# S7CAS-PLEIADES-CARTE-MERE_P20_PLL.net
KiCad netlist of a schematic drawn in Altium Designer
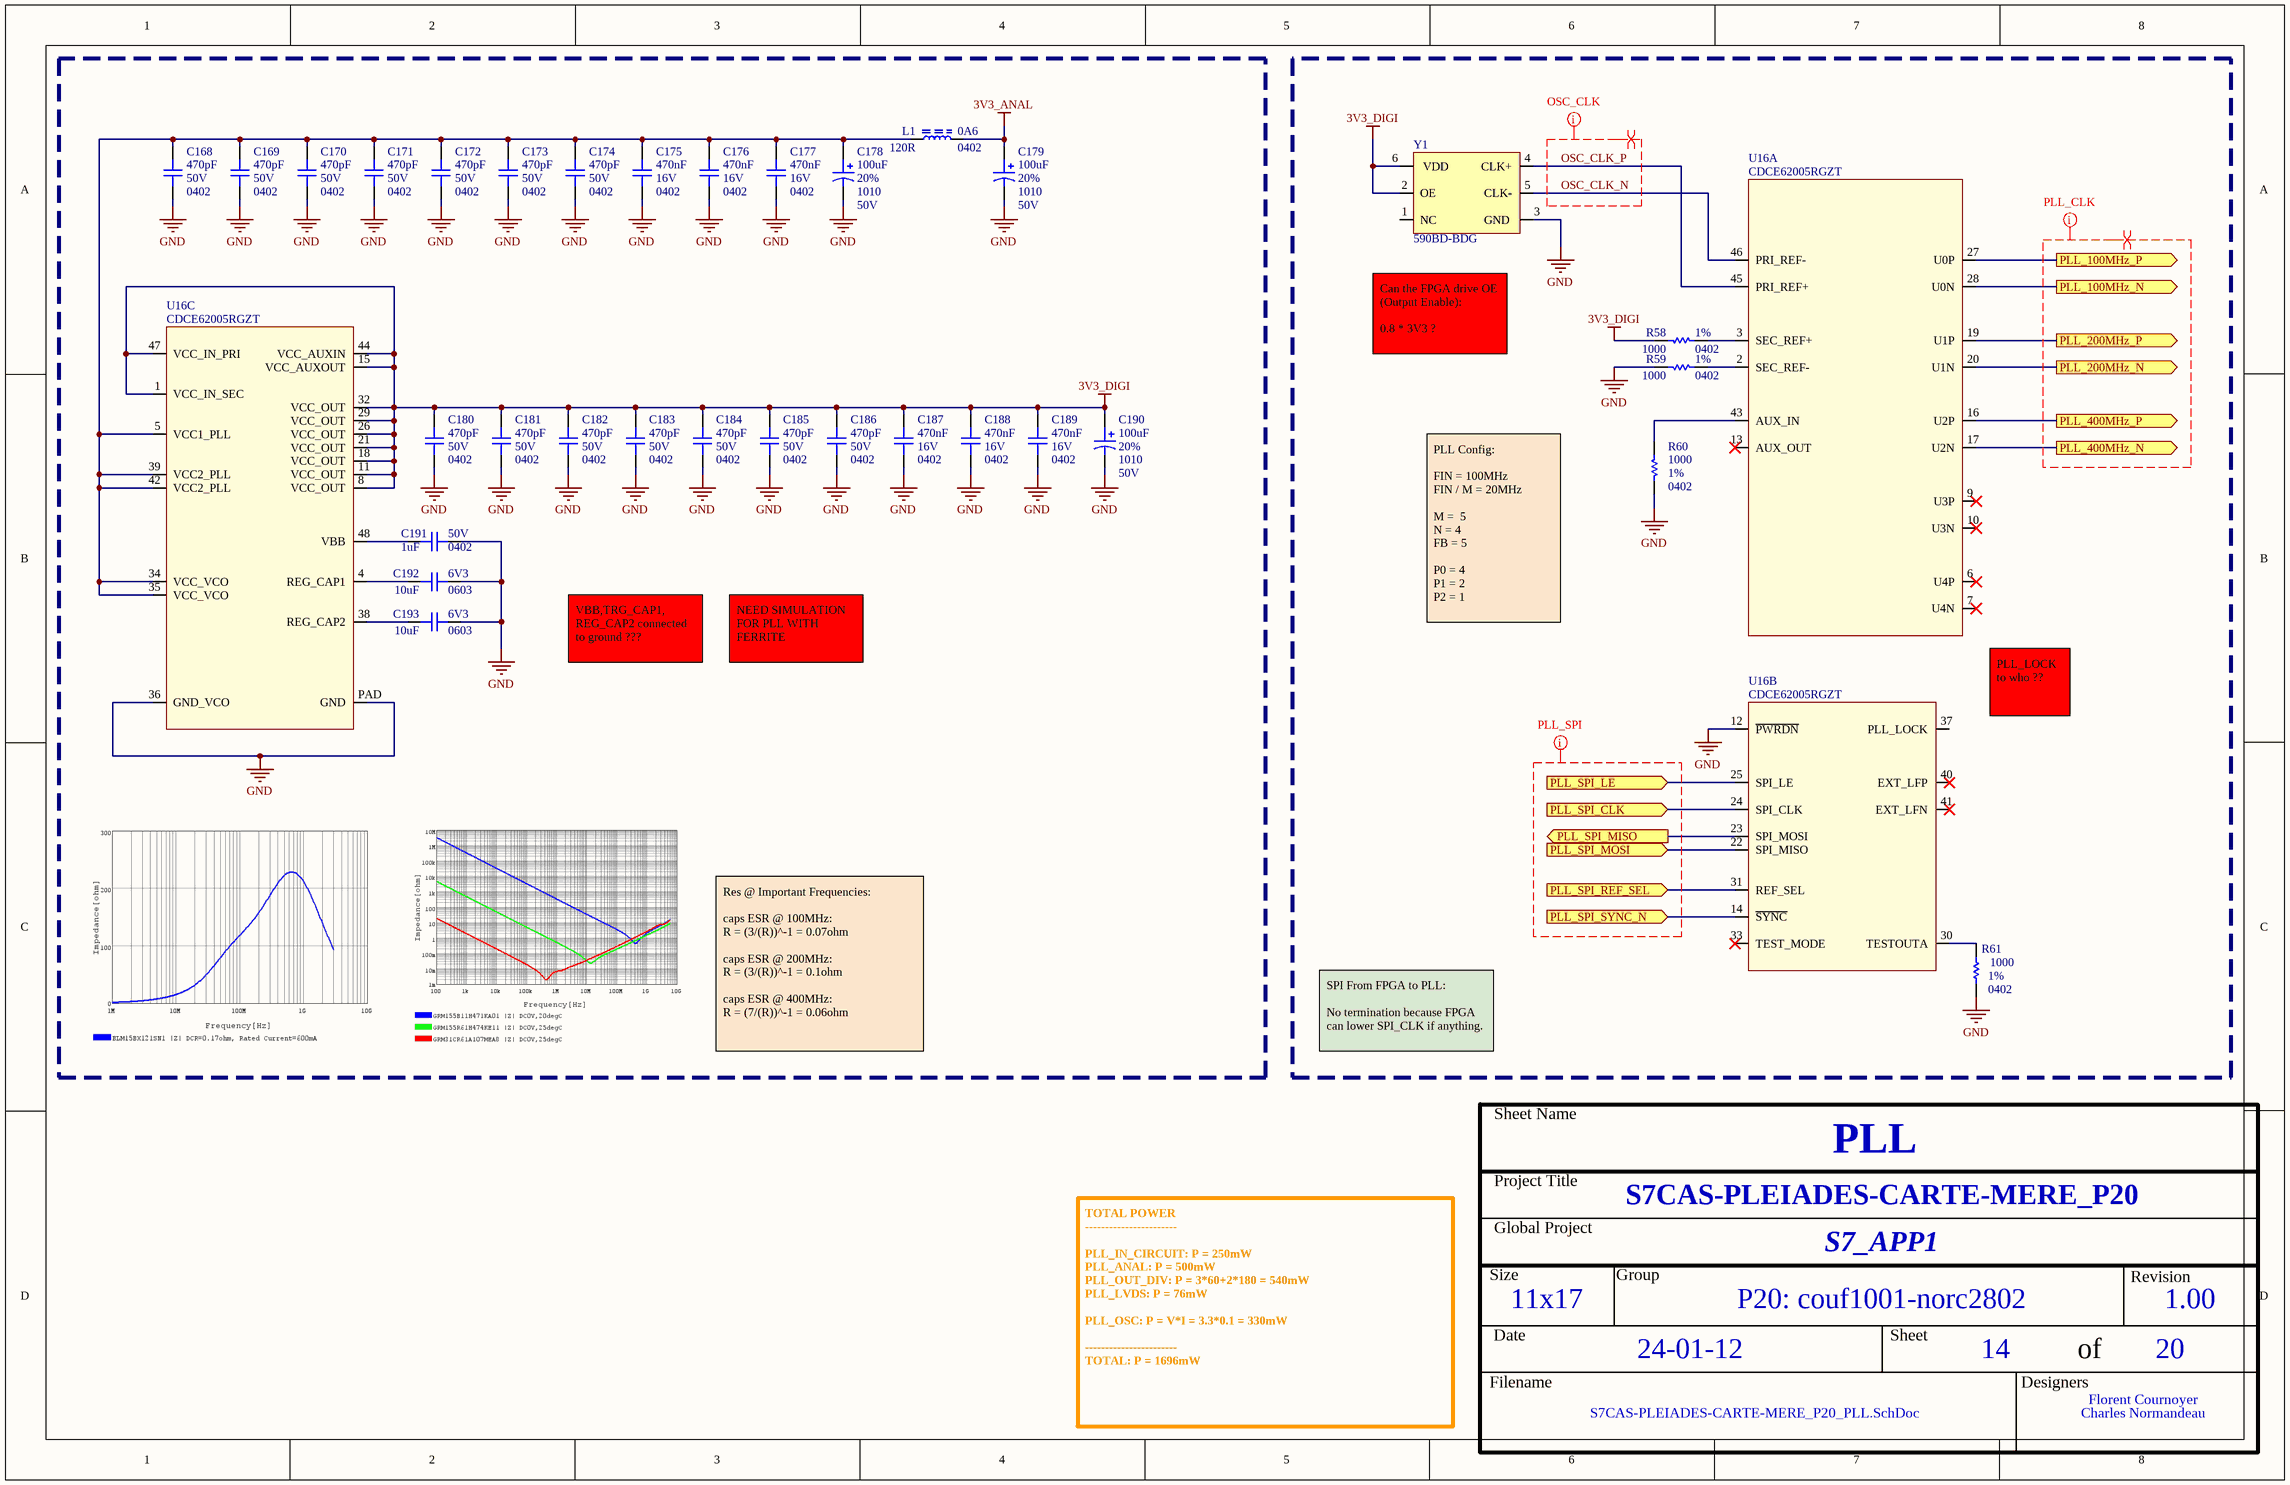
[diagram p0: S7CAS-PLEIADES-CARTE-MERE_P20_PLL.SchDoc]

(export (version "E")
  (design (tool "Eeschema 10.0.6"))
  (components
    (comp (ref "C168")
      (value "470pF")
      (footprint "CAP_0402")
      (description "CAP - 0402")
      (fields
        (field (name "MFG PART NUMBER") "GRM155B11H471KA01")
        (field (name "VOLTAGE") "50V")
        (field (name "PACKAGE") "0402")
        (field (name "CREATEDBY") "Jonathan Bouchard")
      )
      (libsource (lib "S7CAS_LIB2023") (part "CAP - 0402"))
    )
    (comp (ref "C169")
      (value "470pF")
      (footprint "CAP_0402")
      (description "CAP - 0402")
      (fields
        (field (name "MFG PART NUMBER") "GRM155B11H471KA01")
        (field (name "VOLTAGE") "50V")
        (field (name "PACKAGE") "0402")
        (field (name "CREATEDBY") "Jonathan Bouchard")
      )
      (libsource (lib "S7CAS_LIB2023") (part "CAP - 0402"))
    )
    (comp (ref "C170")
      (value "470pF")
      (footprint "CAP_0402")
      (description "CAP - 0402")
      (fields
        (field (name "MFG PART NUMBER") "GRM155B11H471KA01")
        (field (name "VOLTAGE") "50V")
        (field (name "PACKAGE") "0402")
        (field (name "CREATEDBY") "Jonathan Bouchard")
      )
      (libsource (lib "S7CAS_LIB2023") (part "CAP - 0402"))
    )
    (comp (ref "C171")
      (value "470pF")
      (footprint "CAP_0402")
      (description "CAP - 0402")
      (fields
        (field (name "MFG PART NUMBER") "GRM155B11H471KA01")
        (field (name "VOLTAGE") "50V")
        (field (name "PACKAGE") "0402")
        (field (name "CREATEDBY") "Jonathan Bouchard")
      )
      (libsource (lib "S7CAS_LIB2023") (part "CAP - 0402"))
    )
    (comp (ref "C172")
      (value "470pF")
      (footprint "CAP_0402")
      (description "CAP - 0402")
      (fields
        (field (name "MFG PART NUMBER") "GRM155B11H471KA01")
        (field (name "VOLTAGE") "50V")
        (field (name "PACKAGE") "0402")
        (field (name "CREATEDBY") "Jonathan Bouchard")
      )
      (libsource (lib "S7CAS_LIB2023") (part "CAP - 0402"))
    )
    (comp (ref "C173")
      (value "470pF")
      (footprint "CAP_0402")
      (description "CAP - 0402")
      (fields
        (field (name "MFG PART NUMBER") "GRM155B11H471KA01")
        (field (name "VOLTAGE") "50V")
        (field (name "PACKAGE") "0402")
        (field (name "CREATEDBY") "Jonathan Bouchard")
      )
      (libsource (lib "S7CAS_LIB2023") (part "CAP - 0402"))
    )
    (comp (ref "C174")
      (value "470pF")
      (footprint "CAP_0402")
      (description "CAP - 0402")
      (fields
        (field (name "MFG PART NUMBER") "GRM155B11H471KA01")
        (field (name "VOLTAGE") "50V")
        (field (name "PACKAGE") "0402")
        (field (name "CREATEDBY") "Jonathan Bouchard")
      )
      (libsource (lib "S7CAS_LIB2023") (part "CAP - 0402"))
    )
    (comp (ref "C175")
      (value "470nF")
      (footprint "CAP_0402")
      (description "CAP - 0402")
      (fields
        (field (name "MFG PART NUMBER") "GXT155R61C474KE01")
        (field (name "VOLTAGE") "16V")
        (field (name "PACKAGE") "0402")
        (field (name "CREATEDBY") "Jonathan Bouchard")
      )
      (libsource (lib "S7CAS_LIB2023") (part "CAP - 0402"))
    )
    (comp (ref "C176")
      (value "470nF")
      (footprint "CAP_0402")
      (description "CAP - 0402")
      (fields
        (field (name "MFG PART NUMBER") "GXT155R61C474KE01")
        (field (name "VOLTAGE") "16V")
        (field (name "PACKAGE") "0402")
        (field (name "CREATEDBY") "Jonathan Bouchard")
      )
      (libsource (lib "S7CAS_LIB2023") (part "CAP - 0402"))
    )
    (comp (ref "C177")
      (value "470nF")
      (footprint "CAP_0402")
      (description "CAP - 0402")
      (fields
        (field (name "MFG PART NUMBER") "GXT155R61C474KE01")
        (field (name "VOLTAGE") "16V")
        (field (name "PACKAGE") "0402")
        (field (name "CREATEDBY") "Jonathan Bouchard")
      )
      (libsource (lib "S7CAS_LIB2023") (part "CAP - 0402"))
    )
    (comp (ref "C178")
      (value "100uF")
      (footprint "CAP_ALU_1010_vishay")
      (description "CAP - ALU 100uF 20% 50V - 1010")
      (fields
        (field (name "MFG") "Vishay Dale")
        (field (name "MFG PART NUMBER") "MAL215099101E3")
        (field (name "VOLTAGE") "50V")
        (field (name "PACKAGE") "1010")
        (field (name "PRECISION") "20%")
        (field (name "CREATEDBY") "Jonathan Bouchard")
      )
      (libsource (lib "S7CAS_LIB2023") (part "CAP_ALU_MAL215099101E3"))
    )
    (comp (ref "C179")
      (value "100uF")
      (footprint "CAP_ALU_1010_vishay")
      (description "CAP - ALU 100uF 20% 50V - 1010")
      (fields
        (field (name "MFG") "Vishay Dale")
        (field (name "MFG PART NUMBER") "MAL215099101E3")
        (field (name "VOLTAGE") "50V")
        (field (name "PACKAGE") "1010")
        (field (name "PRECISION") "20%")
        (field (name "CREATEDBY") "Jonathan Bouchard")
      )
      (libsource (lib "S7CAS_LIB2023") (part "CAP_ALU_MAL215099101E3"))
    )
    (comp (ref "C180")
      (value "470pF")
      (footprint "CAP_0402")
      (description "CAP - 0402")
      (fields
        (field (name "MFG PART NUMBER") "GRM155B11H471KA01")
        (field (name "VOLTAGE") "50V")
        (field (name "PACKAGE") "0402")
        (field (name "CREATEDBY") "Jonathan Bouchard")
      )
      (libsource (lib "S7CAS_LIB2023") (part "CAP - 0402"))
    )
    (comp (ref "C181")
      (value "470pF")
      (footprint "CAP_0402")
      (description "CAP - 0402")
      (fields
        (field (name "MFG PART NUMBER") "GRM155B11H471KA01")
        (field (name "VOLTAGE") "50V")
        (field (name "PACKAGE") "0402")
        (field (name "CREATEDBY") "Jonathan Bouchard")
      )
      (libsource (lib "S7CAS_LIB2023") (part "CAP - 0402"))
    )
    (comp (ref "C182")
      (value "470pF")
      (footprint "CAP_0402")
      (description "CAP - 0402")
      (fields
        (field (name "MFG PART NUMBER") "GRM155B11H471KA01")
        (field (name "VOLTAGE") "50V")
        (field (name "PACKAGE") "0402")
        (field (name "CREATEDBY") "Jonathan Bouchard")
      )
      (libsource (lib "S7CAS_LIB2023") (part "CAP - 0402"))
    )
    (comp (ref "C183")
      (value "470pF")
      (footprint "CAP_0402")
      (description "CAP - 0402")
      (fields
        (field (name "MFG PART NUMBER") "GRM155B11H471KA01")
        (field (name "VOLTAGE") "50V")
        (field (name "PACKAGE") "0402")
        (field (name "CREATEDBY") "Jonathan Bouchard")
      )
      (libsource (lib "S7CAS_LIB2023") (part "CAP - 0402"))
    )
    (comp (ref "C184")
      (value "470pF")
      (footprint "CAP_0402")
      (description "CAP - 0402")
      (fields
        (field (name "MFG PART NUMBER") "GRM155B11H471KA01")
        (field (name "VOLTAGE") "50V")
        (field (name "PACKAGE") "0402")
        (field (name "CREATEDBY") "Jonathan Bouchard")
      )
      (libsource (lib "S7CAS_LIB2023") (part "CAP - 0402"))
    )
    (comp (ref "C185")
      (value "470pF")
      (footprint "CAP_0402")
      (description "CAP - 0402")
      (fields
        (field (name "MFG PART NUMBER") "GRM155B11H471KA01")
        (field (name "VOLTAGE") "50V")
        (field (name "PACKAGE") "0402")
        (field (name "CREATEDBY") "Jonathan Bouchard")
      )
      (libsource (lib "S7CAS_LIB2023") (part "CAP - 0402"))
    )
    (comp (ref "C186")
      (value "470pF")
      (footprint "CAP_0402")
      (description "CAP - 0402")
      (fields
        (field (name "MFG PART NUMBER") "GRM155B11H471KA01")
        (field (name "VOLTAGE") "50V")
        (field (name "PACKAGE") "0402")
        (field (name "CREATEDBY") "Jonathan Bouchard")
      )
      (libsource (lib "S7CAS_LIB2023") (part "CAP - 0402"))
    )
    (comp (ref "C187")
      (value "470nF")
      (footprint "CAP_0402")
      (description "CAP - 0402")
      (fields
        (field (name "MFG PART NUMBER") "GXT155R61C474KE01")
        (field (name "VOLTAGE") "16V")
        (field (name "PACKAGE") "0402")
        (field (name "CREATEDBY") "Jonathan Bouchard")
      )
      (libsource (lib "S7CAS_LIB2023") (part "CAP - 0402"))
    )
    (comp (ref "C188")
      (value "470nF")
      (footprint "CAP_0402")
      (description "CAP - 0402")
      (fields
        (field (name "MFG PART NUMBER") "GXT155R61C474KE01")
        (field (name "VOLTAGE") "16V")
        (field (name "PACKAGE") "0402")
        (field (name "CREATEDBY") "Jonathan Bouchard")
      )
      (libsource (lib "S7CAS_LIB2023") (part "CAP - 0402"))
    )
    (comp (ref "C189")
      (value "470nF")
      (footprint "CAP_0402")
      (description "CAP - 0402")
      (fields
        (field (name "MFG PART NUMBER") "GXT155R61C474KE01")
        (field (name "VOLTAGE") "16V")
        (field (name "PACKAGE") "0402")
        (field (name "CREATEDBY") "Jonathan Bouchard")
      )
      (libsource (lib "S7CAS_LIB2023") (part "CAP - 0402"))
    )
    (comp (ref "C190")
      (value "100uF")
      (footprint "CAP_ALU_1010_vishay")
      (description "CAP - ALU 100uF 20% 50V - 1010")
      (fields
        (field (name "MFG") "Vishay Dale")
        (field (name "MFG PART NUMBER") "MAL215099101E3")
        (field (name "VOLTAGE") "50V")
        (field (name "PACKAGE") "1010")
        (field (name "PRECISION") "20%")
        (field (name "CREATEDBY") "Jonathan Bouchard")
      )
      (libsource (lib "S7CAS_LIB2023") (part "CAP_ALU_MAL215099101E3"))
    )
    (comp (ref "C191")
      (value "1uF")
      (footprint "CAP_0402")
      (description "CAP - 0402")
      (fields
        (field (name "MFG PART NUMBER") "GXT155R61E105KE01")
        (field (name "VOLTAGE") "50V")
        (field (name "PACKAGE") "0402")
        (field (name "CREATEDBY") "Jonathan Bouchard")
      )
      (libsource (lib "S7CAS_LIB2023") (part "CAP - 0402"))
    )
    (comp (ref "C192")
      (value "10uF")
      (footprint "CAP_0603")
      (description "CAP - 0603")
      (fields
        (field (name "MFG PART NUMBER") "GRM185R60J106ME15")
        (field (name "VOLTAGE") "6V3")
        (field (name "PACKAGE") "0603")
        (field (name "CREATEDBY") "Jonathan Bouchard")
      )
      (libsource (lib "S7CAS_LIB2023") (part "CAP - 0603"))
    )
    (comp (ref "C193")
      (value "10uF")
      (footprint "CAP_0603")
      (description "CAP - 0603")
      (fields
        (field (name "MFG PART NUMBER") "GRM185R60J106ME15")
        (field (name "VOLTAGE") "6V3")
        (field (name "PACKAGE") "0603")
        (field (name "CREATEDBY") "Jonathan Bouchard")
      )
      (libsource (lib "S7CAS_LIB2023") (part "CAP - 0603"))
    )
    (comp (ref "L1")
      (value "120R")
      (footprint "FER_0402")
      (description "FER - 0402")
      (fields
        (field (name "MFG PART NUMBER") "BLM15BX121SN1")
        (field (name "CURRENT") "0A6")
        (field (name "PACKAGE") "0402")
        (field (name "CREATEDBY") "Jonathan Bouchard")
      )
      (libsource (lib "S7CAS_LIB2023") (part "FER - 0402"))
    )
    (comp (ref "R58")
      (value "1000")
      (footprint "RES_0402")
      (description "RES - 0402")
      (fields
        (field (name "VOLTAGE") "50V")
        (field (name "MFG PART NUMBER") "MCS04020C1001FE000")
        (field (name "PACKAGE") "0402")
        (field (name "PRECISION") "1%")
        (field (name "CREATEDBY") "Jonathan Bouchard")
      )
      (libsource (lib "S7CAS_LIB2023") (part "RES - 0402"))
    )
    (comp (ref "R59")
      (value "1000")
      (footprint "RES_0402")
      (description "RES - 0402")
      (fields
        (field (name "VOLTAGE") "50V")
        (field (name "MFG PART NUMBER") "MCS04020C1001FE000")
        (field (name "PACKAGE") "0402")
        (field (name "PRECISION") "1%")
        (field (name "CREATEDBY") "Jonathan Bouchard")
      )
      (libsource (lib "S7CAS_LIB2023") (part "RES - 0402"))
    )
    (comp (ref "R60")
      (value "1000")
      (footprint "RES_0402")
      (description "RES - 0402")
      (fields
        (field (name "VOLTAGE") "50V")
        (field (name "MFG PART NUMBER") "MCS04020C1001FE000")
        (field (name "PACKAGE") "0402")
        (field (name "PRECISION") "1%")
        (field (name "CREATEDBY") "Jonathan Bouchard")
      )
      (libsource (lib "S7CAS_LIB2023") (part "RES - 0402"))
    )
    (comp (ref "R61")
      (value "1000")
      (footprint "RES_0402")
      (description "RES - 0402")
      (fields
        (field (name "VOLTAGE") "50V")
        (field (name "MFG PART NUMBER") "MCS04020C1001FE000")
        (field (name "PACKAGE") "0402")
        (field (name "PRECISION") "1%")
        (field (name "CREATEDBY") "Jonathan Bouchard")
      )
      (libsource (lib "S7CAS_LIB2023") (part "RES - 0402"))
    )
    (comp (ref "U16")
      (value "CDCE62005RGZT")
      (footprint "TIM_CDCE62005RGZT")
      (description "TIM - CLK SYNTH JITTER CLEANER 3:5 - QFN-48")
      (fields
        (field (name "VOLTAGE") "3 V ~ 3.6 V")
        (field (name "MFG") "Texas Instruments")
        (field (name "CREATEDBY") "Jonathan Bouchard")
      )
      (libsource (lib "S7CAS_LIB2023") (part "TIM_CDCE62005RGZT"))
    )
    (comp (ref "Y1")
      (value "590BD-BDG")
      (footprint "OSC_590BD-BDG")
      (description "TIM - OSC PROG 125MHz ~ 214.999MHz LVDS 3.3V 7PPM EN/DS - 6-SMD")
      (fields
        (field (name "CREATEDBY/DATE") "from 590BD-CDG")
        (field (name "VERIFIEDBY") "Caroline Paulin / 3/10/2019")
      )
      (libsource (lib "S7CAS_LIB2023") (part "OSC_590BD-BDG"))
    )
  )
  (nets
    (net (code "1") (name "/OSC_CLK_N") (class "Default")
      (node (ref "U16") (pin "46") (pinfunction "PRI_REF-_46") (pintype "passive"))
      (node (ref "Y1") (pin "5") (pinfunction "CLK-_5") (pintype "passive"))
    )
    (net (code "2") (name "/OSC_CLK_P") (class "Default")
      (node (ref "U16") (pin "45") (pinfunction "PRI_REF+_45") (pintype "passive"))
      (node (ref "Y1") (pin "4") (pinfunction "CLK+_4") (pintype "passive"))
    )
    (net (code "3") (name "/PLL_100MHz_N") (class "Default")
      (node (ref "U16") (pin "28") (pinfunction "U0N_28") (pintype "passive"))
    )
    (net (code "4") (name "/PLL_100MHz_P") (class "Default")
      (node (ref "U16") (pin "27") (pinfunction "U0P_27") (pintype "passive"))
    )
    (net (code "5") (name "/PLL_200MHz_N") (class "Default")
      (node (ref "U16") (pin "20") (pinfunction "U1N_20") (pintype "passive"))
    )
    (net (code "6") (name "/PLL_200MHz_P") (class "Default")
      (node (ref "U16") (pin "19") (pinfunction "U1P_19") (pintype "passive"))
    )
    (net (code "7") (name "/PLL_400MHz_N") (class "Default")
      (node (ref "U16") (pin "17") (pinfunction "U2N_17") (pintype "passive"))
    )
    (net (code "8") (name "/PLL_400MHz_P") (class "Default")
      (node (ref "U16") (pin "16") (pinfunction "U2P_16") (pintype "passive"))
    )
    (net (code "9") (name "/PLL_SPI_CLK") (class "Default")
      (node (ref "U16") (pin "24") (pinfunction "SPI_CLK_24") (pintype "passive"))
    )
    (net (code "10") (name "/PLL_SPI_LE") (class "Default")
      (node (ref "U16") (pin "25") (pinfunction "SPI_LE_25") (pintype "passive"))
    )
    (net (code "11") (name "/PLL_SPI_MISO") (class "Default")
      (node (ref "U16") (pin "23") (pinfunction "SPI_MOSI_23") (pintype "passive"))
    )
    (net (code "12") (name "/PLL_SPI_MOSI") (class "Default")
      (node (ref "U16") (pin "22") (pinfunction "SPI_MISO_22") (pintype "passive"))
    )
    (net (code "13") (name "/PLL_SPI_REF_SEL") (class "Default")
      (node (ref "U16") (pin "31") (pinfunction "REF_SEL_31") (pintype "passive"))
    )
    (net (code "14") (name "/PLL_SPI_SYNC_N") (class "Default")
      (node (ref "U16") (pin "14") (pinfunction "~{SYNC}_14") (pintype "passive"))
    )
    (net (code "15") (name "3V3_ANAL") (class "Default")
      (node (ref "C179") (pin "1") (pinfunction "1_1") (pintype "passive"))
      (node (ref "L1") (pin "1") (pinfunction "1_1") (pintype "passive"))
    )
    (net (code "16") (name "3V3_DIGI") (class "Default")
      (node (ref "C180") (pin "2") (pinfunction "2_2") (pintype "passive"))
      (node (ref "C181") (pin "2") (pinfunction "2_2") (pintype "passive"))
      (node (ref "C182") (pin "2") (pinfunction "2_2") (pintype "passive"))
      (node (ref "C183") (pin "2") (pinfunction "2_2") (pintype "passive"))
      (node (ref "C184") (pin "2") (pinfunction "2_2") (pintype "passive"))
      (node (ref "C185") (pin "2") (pinfunction "2_2") (pintype "passive"))
      (node (ref "C186") (pin "2") (pinfunction "2_2") (pintype "passive"))
      (node (ref "C187") (pin "2") (pinfunction "2_2") (pintype "passive"))
      (node (ref "C188") (pin "2") (pinfunction "2_2") (pintype "passive"))
      (node (ref "C189") (pin "2") (pinfunction "2_2") (pintype "passive"))
      (node (ref "C190") (pin "1") (pinfunction "1_1") (pintype "passive"))
      (node (ref "R58") (pin "2") (pinfunction "2_2") (pintype "passive"))
      (node (ref "U16") (pin "1") (pinfunction "VCC_IN_SEC_1") (pintype "passive"))
      (node (ref "U16") (pin "11") (pinfunction "VCC_OUT_11") (pintype "passive"))
      (node (ref "U16") (pin "15") (pinfunction "VCC_AUXOUT_15") (pintype "passive"))
      (node (ref "U16") (pin "18") (pinfunction "VCC_OUT_18") (pintype "passive"))
      (node (ref "U16") (pin "21") (pinfunction "VCC_OUT_21") (pintype "passive"))
      (node (ref "U16") (pin "26") (pinfunction "VCC_OUT_26") (pintype "passive"))
      (node (ref "U16") (pin "29") (pinfunction "VCC_OUT_29") (pintype "passive"))
      (node (ref "U16") (pin "32") (pinfunction "VCC_OUT_32") (pintype "passive"))
      (node (ref "U16") (pin "44") (pinfunction "VCC_AUXIN_44") (pintype "passive"))
      (node (ref "U16") (pin "47") (pinfunction "VCC_IN_PRI_47") (pintype "passive"))
      (node (ref "U16") (pin "8") (pinfunction "VCC_OUT_8") (pintype "passive"))
      (node (ref "Y1") (pin "2") (pinfunction "OE_2") (pintype "passive"))
      (node (ref "Y1") (pin "6") (pinfunction "VDD_6") (pintype "passive"))
    )
    (net (code "17") (name "GND") (class "Default")
      (node (ref "C168") (pin "1") (pinfunction "1_1") (pintype "passive"))
      (node (ref "C169") (pin "1") (pinfunction "1_1") (pintype "passive"))
      (node (ref "C170") (pin "1") (pinfunction "1_1") (pintype "passive"))
      (node (ref "C171") (pin "1") (pinfunction "1_1") (pintype "passive"))
      (node (ref "C172") (pin "1") (pinfunction "1_1") (pintype "passive"))
      (node (ref "C173") (pin "1") (pinfunction "1_1") (pintype "passive"))
      (node (ref "C174") (pin "1") (pinfunction "1_1") (pintype "passive"))
      (node (ref "C175") (pin "1") (pinfunction "1_1") (pintype "passive"))
      (node (ref "C176") (pin "1") (pinfunction "1_1") (pintype "passive"))
      (node (ref "C177") (pin "1") (pinfunction "1_1") (pintype "passive"))
      (node (ref "C178") (pin "2") (pinfunction "2_2") (pintype "passive"))
      (node (ref "C179") (pin "2") (pinfunction "2_2") (pintype "passive"))
      (node (ref "C180") (pin "1") (pinfunction "1_1") (pintype "passive"))
      (node (ref "C181") (pin "1") (pinfunction "1_1") (pintype "passive"))
      (node (ref "C182") (pin "1") (pinfunction "1_1") (pintype "passive"))
      (node (ref "C183") (pin "1") (pinfunction "1_1") (pintype "passive"))
      (node (ref "C184") (pin "1") (pinfunction "1_1") (pintype "passive"))
      (node (ref "C185") (pin "1") (pinfunction "1_1") (pintype "passive"))
      (node (ref "C186") (pin "1") (pinfunction "1_1") (pintype "passive"))
      (node (ref "C187") (pin "1") (pinfunction "1_1") (pintype "passive"))
      (node (ref "C188") (pin "1") (pinfunction "1_1") (pintype "passive"))
      (node (ref "C189") (pin "1") (pinfunction "1_1") (pintype "passive"))
      (node (ref "C190") (pin "2") (pinfunction "2_2") (pintype "passive"))
      (node (ref "C191") (pin "1") (pinfunction "1_1") (pintype "passive"))
      (node (ref "C192") (pin "1") (pinfunction "1_1") (pintype "passive"))
      (node (ref "C193") (pin "1") (pinfunction "1_1") (pintype "passive"))
      (node (ref "R59") (pin "1") (pinfunction "1_1") (pintype "passive"))
      (node (ref "R60") (pin "2") (pinfunction "2_2") (pintype "passive"))
      (node (ref "R61") (pin "1") (pinfunction "1_1") (pintype "passive"))
      (node (ref "U16") (pin "12") (pinfunction "~{PWRDN}_12") (pintype "passive"))
      (node (ref "U16") (pin "36") (pinfunction "GND_VCO_36") (pintype "passive"))
      (node (ref "U16") (pin "PAD") (pinfunction "GND_PAD") (pintype "passive"))
      (node (ref "Y1") (pin "3") (pinfunction "GND_3") (pintype "passive"))
    )
    (net (code "18") (name "Net-(U16A-AUX_IN)") (class "Default")
      (node (ref "R60") (pin "1") (pinfunction "1_1") (pintype "passive"))
      (node (ref "U16") (pin "43") (pinfunction "AUX_IN_43") (pintype "passive"))
    )
    (net (code "19") (name "Net-(U16A-SEC_REF+)") (class "Default")
      (node (ref "R58") (pin "1") (pinfunction "1_1") (pintype "passive"))
      (node (ref "U16") (pin "3") (pinfunction "SEC_REF+_3") (pintype "passive"))
    )
    (net (code "20") (name "Net-(U16A-SEC_REF-)") (class "Default")
      (node (ref "R59") (pin "2") (pinfunction "2_2") (pintype "passive"))
      (node (ref "U16") (pin "2") (pinfunction "SEC_REF-_2") (pintype "passive"))
    )
    (net (code "21") (name "Net-(U16B-TESTOUTA)") (class "Default")
      (node (ref "R61") (pin "2") (pinfunction "2_2") (pintype "passive"))
      (node (ref "U16") (pin "30") (pinfunction "TESTOUTA_30") (pintype "passive"))
    )
    (net (code "22") (name "Net-(U16C-REG_CAP1)") (class "Default")
      (node (ref "C192") (pin "2") (pinfunction "2_2") (pintype "passive"))
      (node (ref "U16") (pin "4") (pinfunction "REG_CAP1_4") (pintype "passive"))
    )
    (net (code "23") (name "Net-(U16C-REG_CAP2)") (class "Default")
      (node (ref "C193") (pin "2") (pinfunction "2_2") (pintype "passive"))
      (node (ref "U16") (pin "38") (pinfunction "REG_CAP2_38") (pintype "passive"))
    )
    (net (code "24") (name "Net-(U16C-VBB)") (class "Default")
      (node (ref "C191") (pin "2") (pinfunction "2_2") (pintype "passive"))
      (node (ref "U16") (pin "48") (pinfunction "VBB_48") (pintype "passive"))
    )
    (net (code "25") (name "Net-(U16C-VCC1_PLL)") (class "Default")
      (node (ref "C168") (pin "2") (pinfunction "2_2") (pintype "passive"))
      (node (ref "C169") (pin "2") (pinfunction "2_2") (pintype "passive"))
      (node (ref "C170") (pin "2") (pinfunction "2_2") (pintype "passive"))
      (node (ref "C171") (pin "2") (pinfunction "2_2") (pintype "passive"))
      (node (ref "C172") (pin "2") (pinfunction "2_2") (pintype "passive"))
      (node (ref "C173") (pin "2") (pinfunction "2_2") (pintype "passive"))
      (node (ref "C174") (pin "2") (pinfunction "2_2") (pintype "passive"))
      (node (ref "C175") (pin "2") (pinfunction "2_2") (pintype "passive"))
      (node (ref "C176") (pin "2") (pinfunction "2_2") (pintype "passive"))
      (node (ref "C177") (pin "2") (pinfunction "2_2") (pintype "passive"))
      (node (ref "C178") (pin "1") (pinfunction "1_1") (pintype "passive"))
      (node (ref "L1") (pin "2") (pinfunction "2_2") (pintype "passive"))
      (node (ref "U16") (pin "34") (pinfunction "VCC_VCO_34") (pintype "passive"))
      (node (ref "U16") (pin "35") (pinfunction "VCC_VCO_35") (pintype "passive"))
      (node (ref "U16") (pin "39") (pinfunction "VCC2_PLL_39") (pintype "passive"))
      (node (ref "U16") (pin "42") (pinfunction "VCC2_PLL_42") (pintype "passive"))
      (node (ref "U16") (pin "5") (pinfunction "VCC1_PLL_5") (pintype "passive"))
    )
    (net (code "26") (name "unconnected-(U16A-AUX_OUT-Pad13)") (class "Default")
      (node (ref "U16") (pin "13") (pinfunction "AUX_OUT_13") (pintype "passive+no_connect"))
    )
    (net (code "27") (name "unconnected-(U16A-U3N-Pad10)") (class "Default")
      (node (ref "U16") (pin "10") (pinfunction "U3N_10") (pintype "passive+no_connect"))
    )
    (net (code "28") (name "unconnected-(U16A-U3P-Pad9)") (class "Default")
      (node (ref "U16") (pin "9") (pinfunction "U3P_9") (pintype "passive+no_connect"))
    )
    (net (code "29") (name "unconnected-(U16A-U4N-Pad7)") (class "Default")
      (node (ref "U16") (pin "7") (pinfunction "U4N_7") (pintype "passive+no_connect"))
    )
    (net (code "30") (name "unconnected-(U16A-U4P-Pad6)") (class "Default")
      (node (ref "U16") (pin "6") (pinfunction "U4P_6") (pintype "passive+no_connect"))
    )
    (net (code "31") (name "unconnected-(U16B-EXT_LFN-Pad41)") (class "Default")
      (node (ref "U16") (pin "41") (pinfunction "EXT_LFN_41") (pintype "passive+no_connect"))
    )
    (net (code "32") (name "unconnected-(U16B-EXT_LFP-Pad40)") (class "Default")
      (node (ref "U16") (pin "40") (pinfunction "EXT_LFP_40") (pintype "passive+no_connect"))
    )
    (net (code "33") (name "unconnected-(U16B-PLL_LOCK-Pad37)") (class "Default")
      (node (ref "U16") (pin "37") (pinfunction "PLL_LOCK_37") (pintype "passive"))
    )
    (net (code "34") (name "unconnected-(U16B-TEST_MODE-Pad33)") (class "Default")
      (node (ref "U16") (pin "33") (pinfunction "TEST_MODE_33") (pintype "passive+no_connect"))
    )
    (net (code "35") (name "unconnected-(Y1-NC-Pad1)") (class "Default")
      (node (ref "Y1") (pin "1") (pinfunction "NC_1") (pintype "passive"))
    )
  )
)
